# Nanite_85_SS_V2.net
KiCad netlist of a schematic drawn in EAGLE
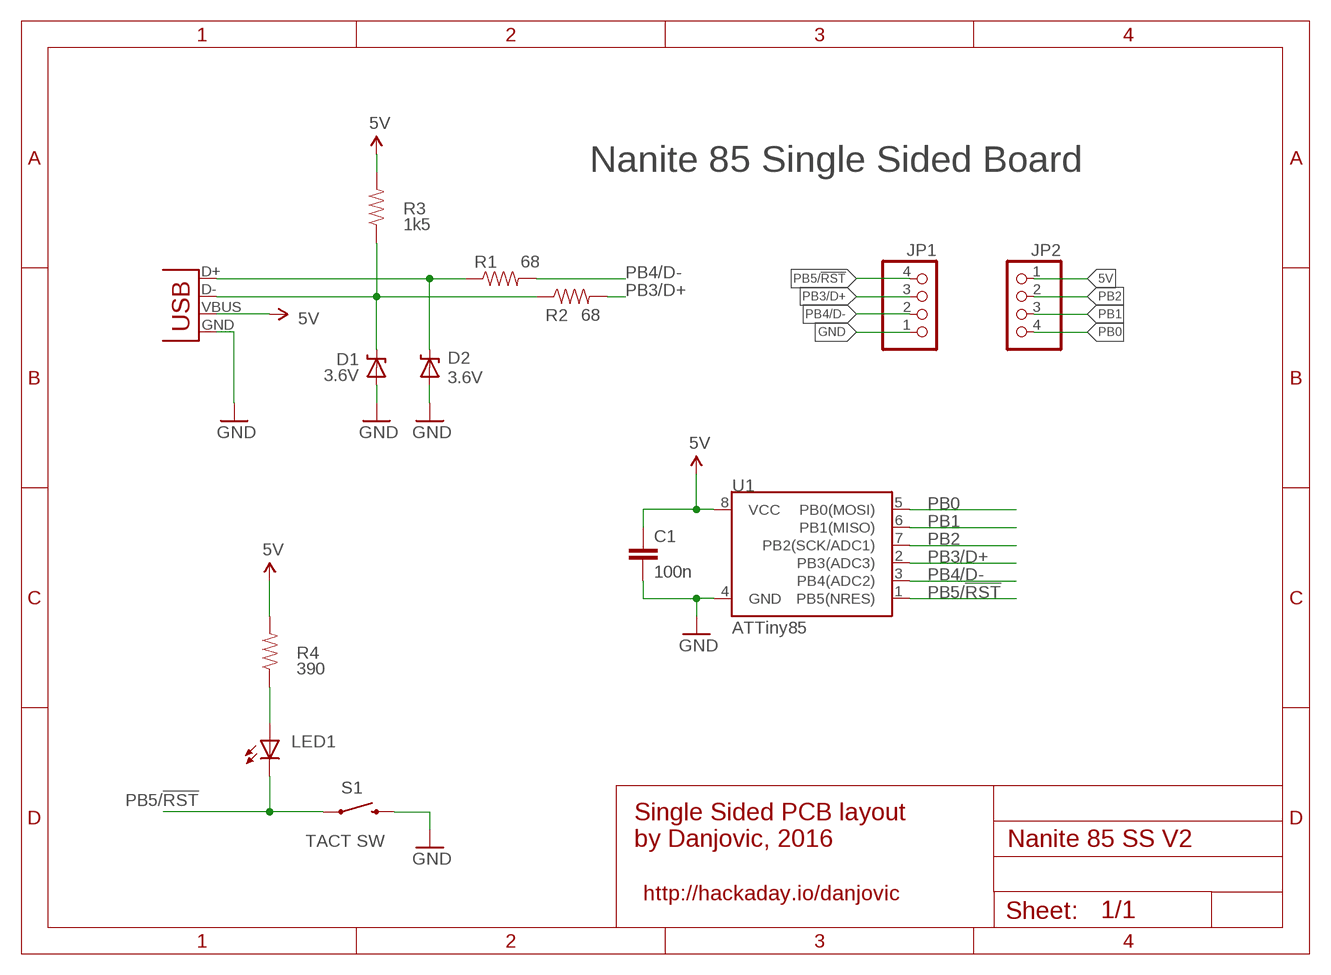
[diagram p0: schematic, sheet 1]

(export (version "E")
  (design (tool "Eeschema 10.0.6"))
  (components
    (comp (ref "C1")
      (value "100n")
      (footprint "eagle-import:CAP-PTH-SMALL-KIT")
      (libsource (lib "eagle-import") (part "CAPKIT"))
    )
    (comp (ref "D1")
      (value "3.6V")
      (footprint "eagle-import:DIODE-ZENER")
      (libsource (lib "eagle-import") (part "DIODE-ZENERPTH"))
    )
    (comp (ref "D2")
      (value "3.6V")
      (footprint "eagle-import:DIODE-ZENER")
      (libsource (lib "eagle-import") (part "DIODE-ZENERPTH"))
    )
    (comp (ref "JP1")
      (value "HEADER-1X4ROUND")
      (footprint "eagle-import:1X04_ROUND")
      (libsource (lib "eagle-import") (part "HEADER-1X4ROUND"))
    )
    (comp (ref "JP2")
      (value "HEADER-1X4ROUND")
      (footprint "eagle-import:1X04_ROUND")
      (libsource (lib "eagle-import") (part "HEADER-1X4ROUND"))
    )
    (comp (ref "JP4")
      (value "USB-B")
      (footprint "eagle-import:USB-B-PTH")
      (libsource (lib "eagle-import") (part "USBPTH"))
    )
    (comp (ref "LED1")
      (value "LED3MM")
      (footprint "eagle-import:LED3MM")
      (libsource (lib "eagle-import") (part "LED3MM"))
    )
    (comp (ref "R1")
      (value "68")
      (footprint "eagle-import:AXIAL-0.3")
      (libsource (lib "eagle-import") (part "RESISTORAXIAL-0.3"))
    )
    (comp (ref "R2")
      (value "68")
      (footprint "eagle-import:AXIAL-0.3EZ")
      (libsource (lib "eagle-import") (part "RESISTOREZ"))
    )
    (comp (ref "R3")
      (value "1k5")
      (footprint "eagle-import:AXIAL-0.3EZ")
      (libsource (lib "eagle-import") (part "RESISTOREZ"))
    )
    (comp (ref "R4")
      (value "390")
      (footprint "eagle-import:AXIAL-0.3EZ")
      (libsource (lib "eagle-import") (part "RESISTOREZ"))
    )
    (comp (ref "S1")
      (value "TACT SW")
      (footprint "eagle-import:TACTILE-PTH")
      (libsource (lib "eagle-import") (part "SWITCH-MOMENTARY-2PTH"))
    )
    (comp (ref "U1")
      (value "ATTiny85")
      (footprint "eagle-import:DIP08")
      (libsource (lib "eagle-import") (part "ATTINY45TINY45-20-DIP"))
    )
  )
  (nets
    (net (code "1") (name "/PB5{slash}~{RST}") (class "Default")
      (node (ref "JP1") (pin "4") (pinfunction "4_4") (pintype "passive"))
      (node (ref "LED1") (pin "K") (pinfunction "C_K") (pintype "passive"))
      (node (ref "S1") (pin "1") (pinfunction "1_1") (pintype "passive"))
      (node (ref "U1") (pin "1") (pinfunction "PB5(NRES)_1") (pintype "bidirectional"))
    )
    (net (code "2") (name "5V") (class "Default")
      (node (ref "C1") (pin "1") (pinfunction "1_1") (pintype "passive"))
      (node (ref "JP2") (pin "1") (pinfunction "1_1") (pintype "passive"))
      (node (ref "JP4") (pin "VBUS") (pinfunction "VBUS_VBUS") (pintype "bidirectional"))
      (node (ref "R3") (pin "P$2") (pinfunction "2_P$2") (pintype "passive"))
      (node (ref "R4") (pin "P$2") (pinfunction "2_P$2") (pintype "passive"))
      (node (ref "U1") (pin "8") (pinfunction "VCC_8") (pintype "bidirectional"))
    )
    (net (code "3") (name "GND") (class "Default")
      (node (ref "C1") (pin "2") (pinfunction "2_2") (pintype "passive"))
      (node (ref "D1") (pin "P$2") (pinfunction "A_P$2") (pintype "passive"))
      (node (ref "D2") (pin "P$2") (pinfunction "A_P$2") (pintype "passive"))
      (node (ref "JP1") (pin "1") (pinfunction "1_1") (pintype "passive"))
      (node (ref "JP4") (pin "GND") (pinfunction "GND_GND") (pintype "bidirectional"))
      (node (ref "S1") (pin "3") (pinfunction "2_3") (pintype "passive"))
      (node (ref "U1") (pin "4") (pinfunction "GND_4") (pintype "bidirectional"))
    )
    (net (code "4") (name "Net-(D1-C)") (class "Default")
      (node (ref "D1") (pin "P$1") (pinfunction "C_P$1") (pintype "passive"))
      (node (ref "JP4") (pin "D-") (pinfunction "D-_D-") (pintype "bidirectional"))
      (node (ref "R2") (pin "P$1") (pinfunction "1_P$1") (pintype "passive"))
      (node (ref "R3") (pin "P$1") (pinfunction "1_P$1") (pintype "passive"))
    )
    (net (code "5") (name "Net-(D2-C)") (class "Default")
      (node (ref "D2") (pin "P$1") (pinfunction "C_P$1") (pintype "passive"))
      (node (ref "JP4") (pin "D+") (pinfunction "D+_D+") (pintype "bidirectional"))
      (node (ref "R1") (pin "P$1") (pinfunction "1_P$1") (pintype "passive"))
    )
    (net (code "6") (name "Net-(R4-1)") (class "Default")
      (node (ref "LED1") (pin "A") (pinfunction "A_A") (pintype "passive"))
      (node (ref "R4") (pin "P$1") (pinfunction "1_P$1") (pintype "passive"))
    )
    (net (code "7") (name "PB0") (class "Default")
      (node (ref "JP2") (pin "4") (pinfunction "4_4") (pintype "passive"))
      (node (ref "U1") (pin "5") (pinfunction "PB0(MOSI)_5") (pintype "bidirectional"))
    )
    (net (code "8") (name "PB1") (class "Default")
      (node (ref "JP2") (pin "3") (pinfunction "3_3") (pintype "passive"))
      (node (ref "U1") (pin "6") (pinfunction "PB1(MISO)_6") (pintype "bidirectional"))
    )
    (net (code "9") (name "PB2") (class "Default")
      (node (ref "JP2") (pin "2") (pinfunction "2_2") (pintype "passive"))
      (node (ref "U1") (pin "7") (pinfunction "PB2(SCK/ADC1)_7") (pintype "bidirectional"))
    )
    (net (code "10") (name "PB3{slash}D+") (class "Default")
      (node (ref "JP1") (pin "3") (pinfunction "3_3") (pintype "passive"))
      (node (ref "R2") (pin "P$2") (pinfunction "2_P$2") (pintype "passive"))
      (node (ref "U1") (pin "2") (pinfunction "PB3(ADC3)_2") (pintype "bidirectional"))
    )
    (net (code "11") (name "PB4{slash}D-") (class "Default")
      (node (ref "JP1") (pin "2") (pinfunction "2_2") (pintype "passive"))
      (node (ref "R1") (pin "P$2") (pinfunction "2_P$2") (pintype "passive"))
      (node (ref "U1") (pin "3") (pinfunction "PB4(ADC2)_3") (pintype "bidirectional"))
    )
  )
)
